# DCPowerSupplies_Design.net
KiCad netlist of a schematic drawn in Altium Designer
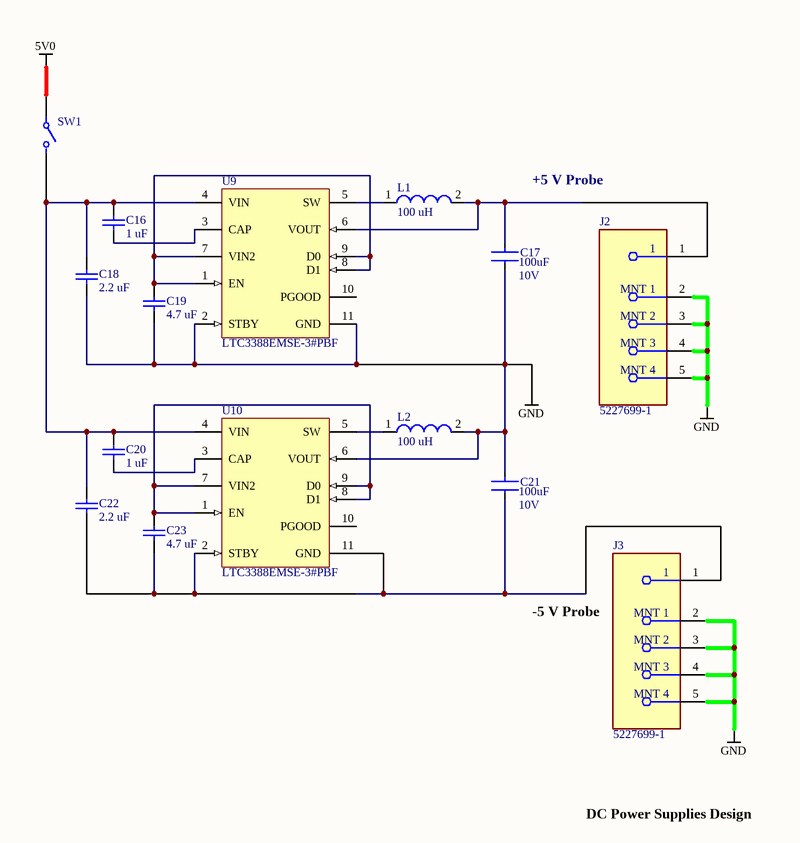
[diagram p0: DCPowerSupplies Design.SchDoc]

(export (version "E")
  (design (tool "Eeschema 10.0.6"))
  (components
    (comp (ref "C16")
      (value "1 uF")
      (footprint "CAPC0603X33X15NL03T05")
      (fields
        (field (name "PART NUMBER") "02016D105MAT2A")
        (field (name "MANUFACTURER") "AVX Interconnect / Elco")
      )
      (libsource (lib "Altium Content Vault") (part "CAP"))
    )
    (comp (ref "C17")
      (value "C5750X5R1A107M280KC")
      (footprint "FP-C5750-280-0_4-MFG")
      (description "CAP CER 100UF 10V X5R 2220")
      (fields
        (field (name "VOLTAGE RATING (DC)") "10V")
        (field (name "CAPACITANCE") "100uF")
        (field (name "TOLERANCE") "20%")
      )
      (libsource (lib "Altium Content Vault") (part "02cd4be3c70576c341d710602a673aa"))
    )
    (comp (ref "C18")
      (value "2.2 uF")
      (footprint "CAPC1608X90X35LL15T15")
      (fields
        (field (name "MANUFACTURER") "AVX Interconnect / Elco")
        (field (name "PART NUMBER") "0603ZD225KAT2A")
      )
      (libsource (lib "Altium Content Vault") (part "CAP"))
    )
    (comp (ref "C19")
      (value "4.7 uF")
      (footprint "CAPC2013X140X50ML20T25")
      (fields
        (field (name "PART NUMBER") "0805ZD475KAT2A")
        (field (name "MANUFACTURER") "AVX Interconnect / Elco")
      )
      (libsource (lib "Altium Content Vault") (part "CAP"))
    )
    (comp (ref "C20")
      (value "1 uF")
      (footprint "CAPC0603X33X15NL03T05")
      (fields
        (field (name "PART NUMBER") "02016D105MAT2A")
        (field (name "MANUFACTURER") "AVX Interconnect / Elco")
      )
      (libsource (lib "Altium Content Vault") (part "CAP"))
    )
    (comp (ref "C21")
      (value "C5750X5R1A107M280KC")
      (footprint "FP-C5750-280-0_4-MFG")
      (description "CAP CER 100UF 10V X5R 2220")
      (fields
        (field (name "VOLTAGE RATING (DC)") "10V")
        (field (name "CAPACITANCE") "100uF")
        (field (name "TOLERANCE") "20%")
      )
      (libsource (lib "Altium Content Vault") (part "02cd4be3c70576c341d710602a673aa"))
    )
    (comp (ref "C22")
      (value "2.2 uF")
      (footprint "CAPC1608X90X35LL15T15")
      (fields
        (field (name "MANUFACTURER") "AVX Interconnect / Elco")
        (field (name "PART NUMBER") "0603ZD225KAT2A")
      )
      (libsource (lib "Altium Content Vault") (part "CAP"))
    )
    (comp (ref "C23")
      (value "4.7 uF")
      (footprint "CAPC2013X140X50ML20T25")
      (fields
        (field (name "PART NUMBER") "0805ZD475KAT2A")
        (field (name "MANUFACTURER") "AVX Interconnect / Elco")
      )
      (libsource (lib "Altium Content Vault") (part "CAP"))
    )
    (comp (ref "J2")
      (value "5227699-1")
      (footprint "FP-5227699-1-MFG")
      (description "CONN BNC JACK STR 50 OHM PCB")
      (libsource (lib "Altium Content Vault") (part "c65b8a639cdaef1819ea20b5466f8fa"))
    )
    (comp (ref "J3")
      (value "5227699-1")
      (footprint "FP-5227699-1-MFG")
      (description "CONN BNC JACK STR 50 OHM PCB")
      (libsource (lib "Altium Content Vault") (part "c65b8a639cdaef1819ea20b5466f8fa"))
    )
    (comp (ref "L1")
      (value "100 uH")
      (footprint "WE-PD3-L")
      (description "SMD Shielded Power Inductor WE-PD3, L = 100 µH")
      (libsource (lib "Altium Content Vault") (part "PAS-IND-INDUCTOR-2"))
    )
    (comp (ref "L2")
      (value "100 uH")
      (footprint "WE-PD3-L")
      (description "SMD Shielded Power Inductor WE-PD3, L = 100 µH")
      (libsource (lib "Altium Content Vault") (part "PAS-IND-INDUCTOR-2"))
    )
    (comp (ref "SW1")
      (value "A8L-11-12N1")
      (footprint "FP-A8L-11-12N1-MFG")
      (description "SWITCH ROCKER SPST 10A 125V")
      (libsource (lib "Altium Content Vault") (part "bb27bde45df87f1f469753f287ef5ae"))
    )
    (comp (ref "U9")
      (value "LTC3388EMSE-3#PBF")
      (footprint "LT-MSE-10-EDP_L")
      (description "20 V High Efficiency Nanopower Step-Down Regulator, 10-pin SOP (MSE-10), -40 to 125 degC, Pb-Free")
      (fields (field (name "MANUFACTURER") "Linear Technology"))
      (libsource (lib "Altium Content Vault") (part "LT-LTC3388-10"))
    )
    (comp (ref "U10")
      (value "LTC3388EMSE-3#PBF")
      (footprint "LT-MSE-10-EDP_L")
      (description "20 V High Efficiency Nanopower Step-Down Regulator, 10-pin SOP (MSE-10), -40 to 125 degC, Pb-Free")
      (fields (field (name "MANUFACTURER") "Linear Technology"))
      (libsource (lib "Altium Content Vault") (part "LT-LTC3388-10"))
    )
  )
  (nets
    (net (code "1") (name "5V0") (class "Default")
      (node (ref "SW1") (pin "1") (pinfunction "1_1") (pintype "passive"))
    )
    (net (code "2") (name "GND") (class "Default")
      (node (ref "C17") (pin "2") (pinfunction "2_2") (pintype "passive"))
      (node (ref "C18") (pin "1") (pinfunction "1_1") (pintype "passive"))
      (node (ref "C19") (pin "1") (pinfunction "1_1") (pintype "passive"))
      (node (ref "C21") (pin "1") (pinfunction "1_1") (pintype "passive"))
      (node (ref "J2") (pin "2") (pinfunction "MNT_1_2") (pintype "passive"))
      (node (ref "J2") (pin "3") (pinfunction "MNT_2_3") (pintype "passive"))
      (node (ref "J2") (pin "4") (pinfunction "MNT_3_4") (pintype "passive"))
      (node (ref "J2") (pin "5") (pinfunction "MNT_4_5") (pintype "passive"))
      (node (ref "J3") (pin "2") (pinfunction "MNT_1_2") (pintype "passive"))
      (node (ref "J3") (pin "3") (pinfunction "MNT_2_3") (pintype "passive"))
      (node (ref "J3") (pin "4") (pinfunction "MNT_3_4") (pintype "passive"))
      (node (ref "J3") (pin "5") (pinfunction "MNT_4_5") (pintype "passive"))
      (node (ref "L2") (pin "2") (pinfunction "2_2") (pintype "passive"))
      (node (ref "U10") (pin "6") (pinfunction "VOUT_6") (pintype "input"))
      (node (ref "U9") (pin "11") (pinfunction "GND_11") (pintype "power_in"))
      (node (ref "U9") (pin "2") (pinfunction "STBY_2") (pintype "input"))
    )
    (net (code "3") (name "Net-(U9-CAP)") (class "Default")
      (node (ref "C16") (pin "1") (pinfunction "1_1") (pintype "passive"))
      (node (ref "U9") (pin "3") (pinfunction "CAP_3") (pintype "passive"))
    )
    (net (code "4") (name "Net-(U9-D0)") (class "Default")
      (node (ref "C19") (pin "2") (pinfunction "2_2") (pintype "passive"))
      (node (ref "U9") (pin "1") (pinfunction "EN_1") (pintype "input"))
      (node (ref "U9") (pin "7") (pinfunction "VIN2_7") (pintype "power_in"))
      (node (ref "U9") (pin "8") (pinfunction "D1_8") (pintype "input"))
      (node (ref "U9") (pin "9") (pinfunction "D0_9") (pintype "input"))
    )
    (net (code "5") (name "Net-(U9-SW)") (class "Default")
      (node (ref "L1") (pin "1") (pinfunction "1_1") (pintype "passive"))
      (node (ref "U9") (pin "5") (pinfunction "SW_5") (pintype "power_in"))
    )
    (net (code "6") (name "Net-(U9-VOUT)") (class "Default")
      (node (ref "C17") (pin "1") (pinfunction "1_1") (pintype "passive"))
      (node (ref "J2") (pin "1") (pinfunction "1_1") (pintype "passive"))
      (node (ref "L1") (pin "2") (pinfunction "2_2") (pintype "passive"))
      (node (ref "U9") (pin "6") (pinfunction "VOUT_6") (pintype "input"))
    )
    (net (code "7") (name "Net-(U10-CAP)") (class "Default")
      (node (ref "C20") (pin "1") (pinfunction "1_1") (pintype "passive"))
      (node (ref "U10") (pin "3") (pinfunction "CAP_3") (pintype "passive"))
    )
    (net (code "8") (name "Net-(U10-D0)") (class "Default")
      (node (ref "C23") (pin "2") (pinfunction "2_2") (pintype "passive"))
      (node (ref "U10") (pin "1") (pinfunction "EN_1") (pintype "input"))
      (node (ref "U10") (pin "7") (pinfunction "VIN2_7") (pintype "power_in"))
      (node (ref "U10") (pin "8") (pinfunction "D1_8") (pintype "input"))
      (node (ref "U10") (pin "9") (pinfunction "D0_9") (pintype "input"))
    )
    (net (code "9") (name "Net-(U10-GND)") (class "Default")
      (node (ref "C21") (pin "2") (pinfunction "2_2") (pintype "passive"))
      (node (ref "C22") (pin "1") (pinfunction "1_1") (pintype "passive"))
      (node (ref "C23") (pin "1") (pinfunction "1_1") (pintype "passive"))
      (node (ref "J3") (pin "1") (pinfunction "1_1") (pintype "passive"))
      (node (ref "U10") (pin "11") (pinfunction "GND_11") (pintype "power_in"))
      (node (ref "U10") (pin "2") (pinfunction "STBY_2") (pintype "input"))
    )
    (net (code "10") (name "Net-(U10-SW)") (class "Default")
      (node (ref "L2") (pin "1") (pinfunction "1_1") (pintype "passive"))
      (node (ref "U10") (pin "5") (pinfunction "SW_5") (pintype "power_in"))
    )
    (net (code "11") (name "Net-(U10-VIN)") (class "Default")
      (node (ref "C16") (pin "2") (pinfunction "2_2") (pintype "passive"))
      (node (ref "C18") (pin "2") (pinfunction "2_2") (pintype "passive"))
      (node (ref "C20") (pin "2") (pinfunction "2_2") (pintype "passive"))
      (node (ref "C22") (pin "2") (pinfunction "2_2") (pintype "passive"))
      (node (ref "SW1") (pin "2") (pinfunction "2_2") (pintype "passive"))
      (node (ref "U10") (pin "4") (pinfunction "VIN_4") (pintype "power_in"))
      (node (ref "U9") (pin "4") (pinfunction "VIN_4") (pintype "power_in"))
    )
    (net (code "12") (name "unconnected-(U9-PGOOD-Pad10)") (class "Default")
      (node (ref "U9") (pin "10") (pinfunction "PGOOD_10") (pintype "tri_state"))
    )
    (net (code "13") (name "unconnected-(U10-PGOOD-Pad10)") (class "Default")
      (node (ref "U10") (pin "10") (pinfunction "PGOOD_10") (pintype "tri_state"))
    )
  )
)
